# ADCAN__sch2.net
KiCad netlist of a schematic drawn in Altium Designer
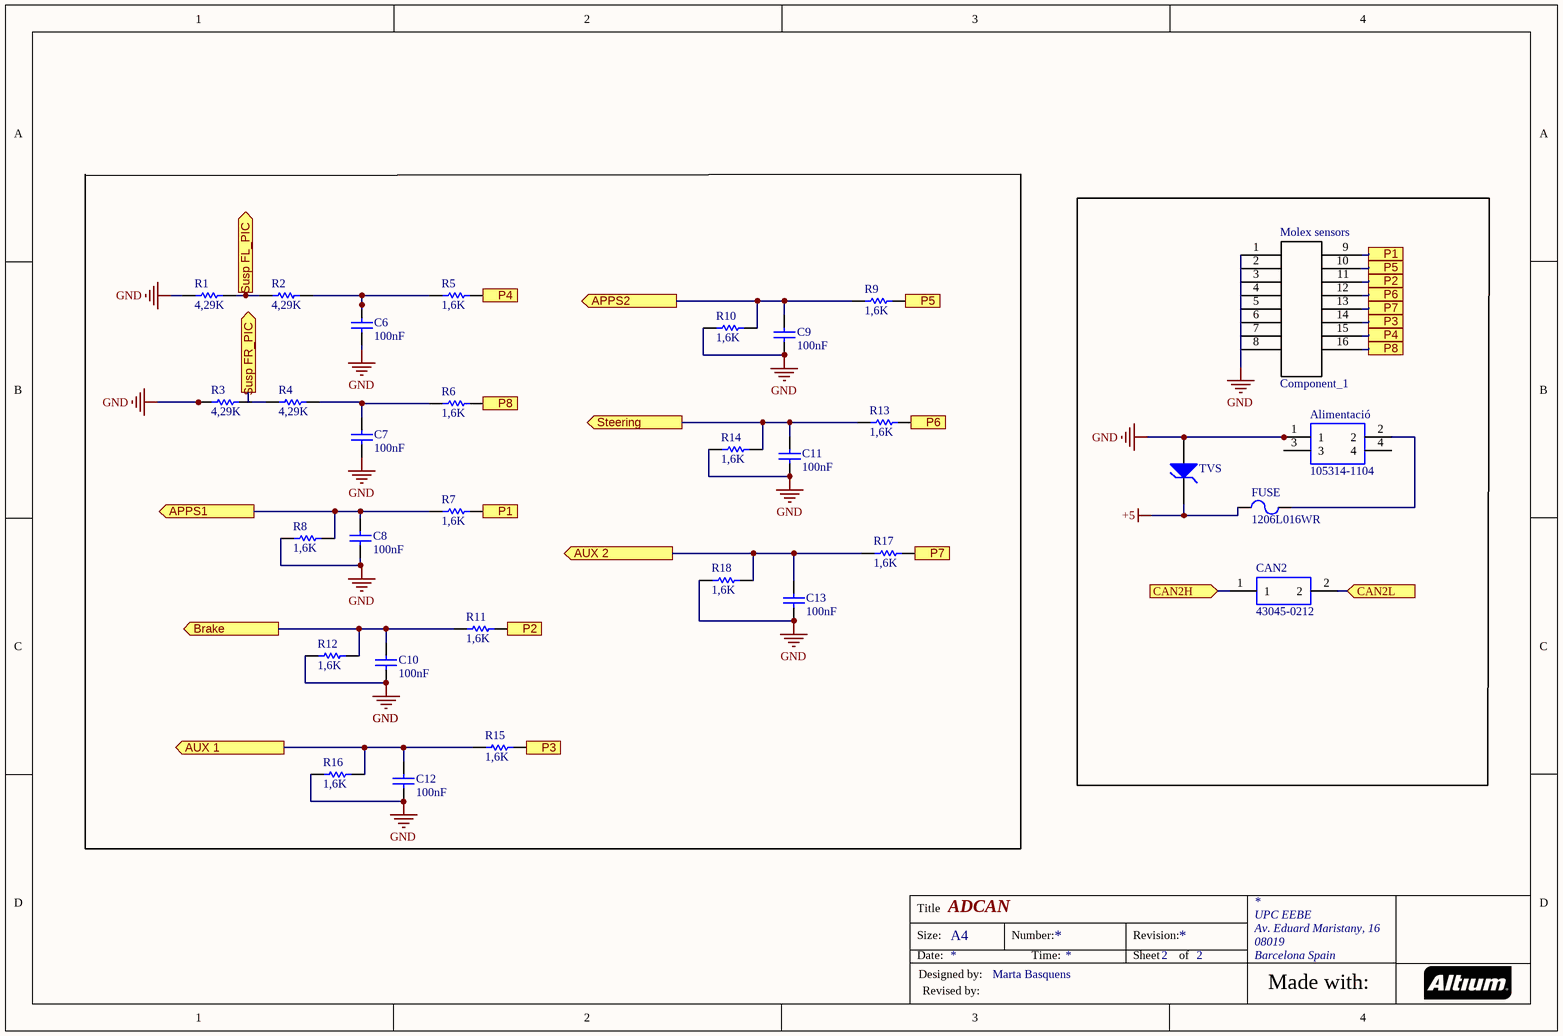
[diagram p0: ADCAN_[sch2].SchDoc]

(export (version "E")
  (design (tool "Eeschema 10.0.6"))
  (components
    (comp (ref "Alimentació")
      (value "105314-1104")
      (footprint "1053141304")
      (description "Molex Nano-Fit 105314, 2.5mm Pitch, 4 Way, 2 Row, Right Angle PCB Header, Through Hole")
      (fields (field (name "RS PART NUMBER") "1623690"))
      (libsource (lib "105314-1104") (part "105314-1104"))
    )
    (comp (ref "C6")
      (value "100nF")
      (footprint "CAPC3216X102X94LL20")
      (description "Chip Capacitor, 1.05 nF, +/- 12%, 14 V, -55 to 125 degC, 1206 (3216 Metric), RoHS, Tape and Reel")
      (fields (field (name "MANUFACTURER") "AVX"))
      (libsource (lib "Altium Content Vault") (part "CAP-NP-2"))
    )
    (comp (ref "C7")
      (value "100nF")
      (footprint "CAPC3216X102X94LL20")
      (description "Chip Capacitor, 1.05 nF, +/- 12%, 14 V, -55 to 125 degC, 1206 (3216 Metric), RoHS, Tape and Reel")
      (fields (field (name "MANUFACTURER") "AVX"))
      (libsource (lib "Altium Content Vault") (part "CAP-NP-2"))
    )
    (comp (ref "C8")
      (value "100nF")
      (footprint "CAPC3216X102X94LL20")
      (description "Chip Capacitor, 1.05 nF, +/- 12%, 14 V, -55 to 125 degC, 1206 (3216 Metric), RoHS, Tape and Reel")
      (fields (field (name "MANUFACTURER") "AVX"))
      (libsource (lib "Altium Content Vault") (part "CAP-NP-2"))
    )
    (comp (ref "C9")
      (value "100nF")
      (footprint "CAPC3216X102X94LL20")
      (description "Chip Capacitor, 1.05 nF, +/- 12%, 14 V, -55 to 125 degC, 1206 (3216 Metric), RoHS, Tape and Reel")
      (fields (field (name "MANUFACTURER") "AVX"))
      (libsource (lib "Altium Content Vault") (part "CAP-NP-2"))
    )
    (comp (ref "C10")
      (value "100nF")
      (footprint "CAPC3216X102X94LL20")
      (description "Chip Capacitor, 1.05 nF, +/- 12%, 14 V, -55 to 125 degC, 1206 (3216 Metric), RoHS, Tape and Reel")
      (fields (field (name "MANUFACTURER") "AVX"))
      (libsource (lib "Altium Content Vault") (part "CAP-NP-2"))
    )
    (comp (ref "C11")
      (value "100nF")
      (footprint "CAPC3216X102X94LL20")
      (description "Chip Capacitor, 1.05 nF, +/- 12%, 14 V, -55 to 125 degC, 1206 (3216 Metric), RoHS, Tape and Reel")
      (fields (field (name "MANUFACTURER") "AVX"))
      (libsource (lib "Altium Content Vault") (part "CAP-NP-2"))
    )
    (comp (ref "C12")
      (value "100nF")
      (footprint "CAPC3216X102X94LL20")
      (description "Chip Capacitor, 1.05 nF, +/- 12%, 14 V, -55 to 125 degC, 1206 (3216 Metric), RoHS, Tape and Reel")
      (fields (field (name "MANUFACTURER") "AVX"))
      (libsource (lib "Altium Content Vault") (part "CAP-NP-2"))
    )
    (comp (ref "C13")
      (value "100nF")
      (footprint "CAPC3216X102X94LL20")
      (description "Chip Capacitor, 1.05 nF, +/- 12%, 14 V, -55 to 125 degC, 1206 (3216 Metric), RoHS, Tape and Reel")
      (fields (field (name "MANUFACTURER") "AVX"))
      (libsource (lib "Altium Content Vault") (part "CAP-NP-2"))
    )
    (comp (ref "CAN2")
      (value "43045-0212")
      (footprint "0430450212")
      (fields (field (name "RS PART NUMBER") "2332860P"))
      (libsource (lib "43045-0212") (part "43045-0212"))
    )
    (comp (ref "FUSE")
      (value "1206L016WR")
      (footprint "LFUS-1206L016WR_V")
      (description "Resettable Fuse, 30 V, 100 A, 4.5 Ohm, -40 to 85 degC, 1206 (3216 Metric), RoHS, Tape and Reel")
      (fields (field (name "MANUFACTURER") "Littelfuse"))
      (libsource (lib "Altium Content Vault") (part "FUSE-2"))
    )
    (comp (ref "Molex sensors")
      (value "Component_1")
      (footprint "Molex8x2:PCBComponent_1")
      (libsource (lib "Molex8x2") (part "Component_1"))
    )
    (comp (ref "R1")
      (value "4,29K")
      (footprint "RESC1206(3216)_L")
      (description "22K 0.25W 1% 1206 (3216 Metric)  SMD")
      (fields (field (name "TOLERANCE") "1 %") (field (name "POWER") "0.25 W"))
      (libsource (lib "") (part "RES_1"))
    )
    (comp (ref "R2")
      (value "4,29K")
      (footprint "RESC1206(3216)_L")
      (description "22K 0.25W 1% 1206 (3216 Metric)  SMD")
      (fields (field (name "TOLERANCE") "1 %") (field (name "POWER") "0.25 W"))
      (libsource (lib "") (part "RES_1"))
    )
    (comp (ref "R3")
      (value "4,29K")
      (footprint "RESC1206(3216)_L")
      (description "22K 0.25W 1% 1206 (3216 Metric)  SMD")
      (fields (field (name "TOLERANCE") "1 %") (field (name "POWER") "0.25 W"))
      (libsource (lib "") (part "RES_2"))
    )
    (comp (ref "R4")
      (value "4,29K")
      (footprint "RESC1206(3216)_L")
      (description "22K 0.25W 1% 1206 (3216 Metric)  SMD")
      (fields (field (name "TOLERANCE") "1 %") (field (name "POWER") "0.25 W"))
      (libsource (lib "") (part "RES_3"))
    )
    (comp (ref "R5")
      (value "1,6K")
      (footprint "RESC1206(3216)_L")
      (description "22K 0.25W 1% 1206 (3216 Metric)  SMD")
      (fields (field (name "TOLERANCE") "1 %") (field (name "POWER") "0.25 W"))
      (libsource (lib "Altium Content Vault") (part "RES"))
    )
    (comp (ref "R6")
      (value "1,6K")
      (footprint "RESC1206(3216)_L")
      (description "22K 0.25W 1% 1206 (3216 Metric)  SMD")
      (fields (field (name "TOLERANCE") "1 %") (field (name "POWER") "0.25 W"))
      (libsource (lib "Altium Content Vault") (part "RES"))
    )
    (comp (ref "R7")
      (value "1,6K")
      (footprint "RESC1206(3216)_L")
      (description "22K 0.25W 1% 1206 (3216 Metric)  SMD")
      (fields (field (name "TOLERANCE") "1 %") (field (name "POWER") "0.25 W"))
      (libsource (lib "Altium Content Vault") (part "RES"))
    )
    (comp (ref "R8")
      (value "1,6K")
      (footprint "RESC1206(3216)_L")
      (description "22K 0.25W 1% 1206 (3216 Metric)  SMD")
      (fields (field (name "TOLERANCE") "1 %") (field (name "POWER") "0.25 W"))
      (libsource (lib "Altium Content Vault") (part "RES"))
    )
    (comp (ref "R9")
      (value "1,6K")
      (footprint "RESC1206(3216)_L")
      (description "22K 0.25W 1% 1206 (3216 Metric)  SMD")
      (fields (field (name "TOLERANCE") "1 %") (field (name "POWER") "0.25 W"))
      (libsource (lib "Altium Content Vault") (part "RES"))
    )
    (comp (ref "R10")
      (value "1,6K")
      (footprint "RESC1206(3216)_L")
      (description "22K 0.25W 1% 1206 (3216 Metric)  SMD")
      (fields (field (name "TOLERANCE") "1 %") (field (name "POWER") "0.25 W"))
      (libsource (lib "Altium Content Vault") (part "RES"))
    )
    (comp (ref "R11")
      (value "1,6K")
      (footprint "RESC1206(3216)_L")
      (description "22K 0.25W 1% 1206 (3216 Metric)  SMD")
      (fields (field (name "TOLERANCE") "1 %") (field (name "POWER") "0.25 W"))
      (libsource (lib "Altium Content Vault") (part "RES"))
    )
    (comp (ref "R12")
      (value "1,6K")
      (footprint "RESC1206(3216)_L")
      (description "22K 0.25W 1% 1206 (3216 Metric)  SMD")
      (fields (field (name "TOLERANCE") "1 %") (field (name "POWER") "0.25 W"))
      (libsource (lib "Altium Content Vault") (part "RES"))
    )
    (comp (ref "R13")
      (value "1,6K")
      (footprint "RESC1206(3216)_L")
      (description "22K 0.25W 1% 1206 (3216 Metric)  SMD")
      (fields (field (name "TOLERANCE") "1 %") (field (name "POWER") "0.25 W"))
      (libsource (lib "Altium Content Vault") (part "RES"))
    )
    (comp (ref "R14")
      (value "1,6K")
      (footprint "RESC1206(3216)_L")
      (description "22K 0.25W 1% 1206 (3216 Metric)  SMD")
      (fields (field (name "TOLERANCE") "1 %") (field (name "POWER") "0.25 W"))
      (libsource (lib "Altium Content Vault") (part "RES"))
    )
    (comp (ref "R15")
      (value "1,6K")
      (footprint "RESC1206(3216)_L")
      (description "22K 0.25W 1% 1206 (3216 Metric)  SMD")
      (fields (field (name "TOLERANCE") "1 %") (field (name "POWER") "0.25 W"))
      (libsource (lib "Altium Content Vault") (part "RES"))
    )
    (comp (ref "R16")
      (value "1,6K")
      (footprint "RESC1206(3216)_L")
      (description "22K 0.25W 1% 1206 (3216 Metric)  SMD")
      (fields (field (name "TOLERANCE") "1 %") (field (name "POWER") "0.25 W"))
      (libsource (lib "Altium Content Vault") (part "RES"))
    )
    (comp (ref "R17")
      (value "1,6K")
      (footprint "RESC1206(3216)_L")
      (description "22K 0.25W 1% 1206 (3216 Metric)  SMD")
      (fields (field (name "TOLERANCE") "1 %") (field (name "POWER") "0.25 W"))
      (libsource (lib "Altium Content Vault") (part "RES"))
    )
    (comp (ref "R18")
      (value "1,6K")
      (footprint "RESC1206(3216)_L")
      (description "22K 0.25W 1% 1206 (3216 Metric)  SMD")
      (fields (field (name "TOLERANCE") "1 %") (field (name "POWER") "0.25 W"))
      (libsource (lib "Altium Content Vault") (part "RES"))
    )
    (comp (ref "TVS")
      (value "~")
      (footprint "ONSC-SMB-2-403A-03_J_V")
      (description "TVS ZENER UNIDIR 600W 27V SMB")
      (fields (field (name "PARTNUMBER") "P6SMB27AT3G"))
      (libsource (lib "Altium Content Vault") (part "Zener-AC-2"))
    )
  )
  (nets
    (net (code "1") (name "+5") (class "Default")
      (node (ref "FUSE") (pin "1") (pinfunction "1_1") (pintype "passive"))
      (node (ref "TVS") (pin "C") (pinfunction "C_C") (pintype "passive"))
    )
    (net (code "2") (name "/APPS1") (class "Default")
      (node (ref "C8") (pin "2") (pinfunction "2_2") (pintype "passive"))
      (node (ref "R7") (pin "2") (pinfunction "2_2") (pintype "passive"))
      (node (ref "R8") (pin "1") (pinfunction "1_1") (pintype "passive"))
    )
    (net (code "3") (name "/APPS2") (class "Default")
      (node (ref "C9") (pin "2") (pinfunction "2_2") (pintype "passive"))
      (node (ref "R10") (pin "1") (pinfunction "1_1") (pintype "passive"))
      (node (ref "R9") (pin "2") (pinfunction "2_2") (pintype "passive"))
    )
    (net (code "4") (name "/AUX 1") (class "Default")
      (node (ref "C12") (pin "2") (pinfunction "2_2") (pintype "passive"))
      (node (ref "R15") (pin "2") (pinfunction "2_2") (pintype "passive"))
      (node (ref "R16") (pin "1") (pinfunction "1_1") (pintype "passive"))
    )
    (net (code "5") (name "/AUX 2") (class "Default")
      (node (ref "C13") (pin "2") (pinfunction "2_2") (pintype "passive"))
      (node (ref "R17") (pin "2") (pinfunction "2_2") (pintype "passive"))
      (node (ref "R18") (pin "1") (pinfunction "1_1") (pintype "passive"))
    )
    (net (code "6") (name "/Brake") (class "Default")
      (node (ref "C10") (pin "2") (pinfunction "2_2") (pintype "passive"))
      (node (ref "R11") (pin "2") (pinfunction "2_2") (pintype "passive"))
      (node (ref "R12") (pin "1") (pinfunction "1_1") (pintype "passive"))
    )
    (net (code "7") (name "/CAN2H") (class "Default")
      (node (ref "CAN2") (pin "1") (pinfunction "1_1") (pintype "passive"))
    )
    (net (code "8") (name "/CAN2L") (class "Default")
      (node (ref "CAN2") (pin "2") (pinfunction "2_2") (pintype "passive"))
    )
    (net (code "9") (name "/P1") (class "Default")
      (node (ref "R7") (pin "1") (pinfunction "1_1") (pintype "passive"))
    )
    (net (code "10") (name "/P2") (class "Default")
      (node (ref "R11") (pin "1") (pinfunction "1_1") (pintype "passive"))
    )
    (net (code "11") (name "/P3") (class "Default")
      (node (ref "R15") (pin "1") (pinfunction "1_1") (pintype "passive"))
    )
    (net (code "12") (name "/P4") (class "Default")
      (node (ref "R5") (pin "1") (pinfunction "1_1") (pintype "passive"))
    )
    (net (code "13") (name "/P5") (class "Default")
      (node (ref "R9") (pin "1") (pinfunction "1_1") (pintype "passive"))
    )
    (net (code "14") (name "/P6") (class "Default")
      (node (ref "R13") (pin "1") (pinfunction "1_1") (pintype "passive"))
    )
    (net (code "15") (name "/P7") (class "Default")
      (node (ref "R17") (pin "1") (pinfunction "1_1") (pintype "passive"))
    )
    (net (code "16") (name "/P8") (class "Default")
      (node (ref "R6") (pin "1") (pinfunction "1_1") (pintype "passive"))
    )
    (net (code "17") (name "/Steering") (class "Default")
      (node (ref "C11") (pin "2") (pinfunction "2_2") (pintype "passive"))
      (node (ref "R13") (pin "2") (pinfunction "2_2") (pintype "passive"))
      (node (ref "R14") (pin "1") (pinfunction "1_1") (pintype "passive"))
    )
    (net (code "18") (name "/Susp FL_PIC") (class "Default")
      (node (ref "R1") (pin "2") (pinfunction "2_2") (pintype "passive"))
      (node (ref "R2") (pin "1") (pinfunction "1_1") (pintype "passive"))
    )
    (net (code "20") (name "GND") (class "Default")
      (node (ref "Alimentació") (pin "1") (pinfunction "1_1") (pintype "passive"))
      (node (ref "C10") (pin "1") (pinfunction "1_1") (pintype "passive"))
      (node (ref "C11") (pin "1") (pinfunction "1_1") (pintype "passive"))
      (node (ref "C12") (pin "1") (pinfunction "1_1") (pintype "passive"))
      (node (ref "C13") (pin "1") (pinfunction "1_1") (pintype "passive"))
      (node (ref "C6") (pin "1") (pinfunction "1_1") (pintype "passive"))
      (node (ref "C7") (pin "1") (pinfunction "1_1") (pintype "passive"))
      (node (ref "C8") (pin "1") (pinfunction "1_1") (pintype "passive"))
      (node (ref "C9") (pin "1") (pinfunction "1_1") (pintype "passive"))
      (node (ref "R1") (pin "1") (pinfunction "1_1") (pintype "passive"))
      (node (ref "R10") (pin "2") (pinfunction "2_2") (pintype "passive"))
      (node (ref "R12") (pin "2") (pinfunction "2_2") (pintype "passive"))
      (node (ref "R14") (pin "2") (pinfunction "2_2") (pintype "passive"))
      (node (ref "R16") (pin "2") (pinfunction "2_2") (pintype "passive"))
      (node (ref "R18") (pin "2") (pinfunction "2_2") (pintype "passive"))
      (node (ref "R3") (pin "1") (pinfunction "1_1") (pintype "passive"))
      (node (ref "R8") (pin "2") (pinfunction "2_2") (pintype "passive"))
      (node (ref "TVS") (pin "A") (pinfunction "A_A") (pintype "passive"))
    )
    (net (code "21") (name "Net-(Alimentació-Pad2)") (class "Default")
      (node (ref "Alimentació") (pin "2") (pinfunction "2_2") (pintype "passive"))
      (node (ref "FUSE") (pin "2") (pinfunction "2_2") (pintype "passive"))
    )
    (net (code "22") (name "Net-(C6-Pad2)") (class "Default")
      (node (ref "C6") (pin "2") (pinfunction "2_2") (pintype "passive"))
      (node (ref "R2") (pin "2") (pinfunction "2_2") (pintype "passive"))
      (node (ref "R5") (pin "2") (pinfunction "2_2") (pintype "passive"))
    )
    (net (code "23") (name "Net-(C7-Pad2)") (class "Default")
      (node (ref "C7") (pin "2") (pinfunction "2_2") (pintype "passive"))
      (node (ref "R4") (pin "2") (pinfunction "2_2") (pintype "passive"))
      (node (ref "R6") (pin "2") (pinfunction "2_2") (pintype "passive"))
    )
    (net (code "24") (name "Net-(R3-Pad1)") (class "Default")
      (node (ref "R3") (pin "1") (pinfunction "1_1") (pintype "passive"))
      (node (ref "R4") (pin "2") (pinfunction "2_2") (pintype "passive"))
    )
    (net (code "25") (name "unconnected-(Alimentació-Pad3)") (class "Default")
      (node (ref "Alimentació") (pin "3") (pinfunction "3_3") (pintype "passive"))
    )
    (net (code "26") (name "unconnected-(Alimentació-Pad4)") (class "Default")
      (node (ref "Alimentació") (pin "4") (pinfunction "4_4") (pintype "passive"))
    )
    (net (code "27") (name "unconnected-(Molex sensors-Pad1)") (class "Default")
      (node (ref "Molex sensors") (pin "1") (pintype "passive"))
    )
    (net (code "28") (name "unconnected-(Molex sensors-Pad2)") (class "Default")
      (node (ref "Molex sensors") (pin "2") (pintype "passive"))
    )
    (net (code "29") (name "unconnected-(Molex sensors-Pad3)") (class "Default")
      (node (ref "Molex sensors") (pin "3") (pintype "passive"))
    )
    (net (code "30") (name "unconnected-(Molex sensors-Pad4)") (class "Default")
      (node (ref "Molex sensors") (pin "4") (pintype "passive"))
    )
    (net (code "31") (name "unconnected-(Molex sensors-Pad5)") (class "Default")
      (node (ref "Molex sensors") (pin "5") (pintype "passive"))
    )
    (net (code "32") (name "unconnected-(Molex sensors-Pad6)") (class "Default")
      (node (ref "Molex sensors") (pin "6") (pintype "passive"))
    )
    (net (code "33") (name "unconnected-(Molex sensors-Pad7)") (class "Default")
      (node (ref "Molex sensors") (pin "7") (pintype "passive"))
    )
    (net (code "34") (name "unconnected-(Molex sensors-Pad8)") (class "Default")
      (node (ref "Molex sensors") (pin "8") (pintype "passive"))
    )
    (net (code "35") (name "unconnected-(Molex sensors-Pad9)") (class "Default")
      (node (ref "Molex sensors") (pin "9") (pintype "passive"))
    )
    (net (code "36") (name "unconnected-(Molex sensors-Pad10)") (class "Default")
      (node (ref "Molex sensors") (pin "10") (pintype "passive"))
    )
    (net (code "37") (name "unconnected-(Molex sensors-Pad11)") (class "Default")
      (node (ref "Molex sensors") (pin "11") (pintype "passive"))
    )
    (net (code "38") (name "unconnected-(Molex sensors-Pad12)") (class "Default")
      (node (ref "Molex sensors") (pin "12") (pintype "passive"))
    )
    (net (code "39") (name "unconnected-(Molex sensors-Pad13)") (class "Default")
      (node (ref "Molex sensors") (pin "13") (pintype "passive"))
    )
    (net (code "40") (name "unconnected-(Molex sensors-Pad14)") (class "Default")
      (node (ref "Molex sensors") (pin "14") (pintype "passive"))
    )
    (net (code "41") (name "unconnected-(Molex sensors-Pad15)") (class "Default")
      (node (ref "Molex sensors") (pin "15") (pintype "passive"))
    )
    (net (code "42") (name "unconnected-(Molex sensors-Pad16)") (class "Default")
      (node (ref "Molex sensors") (pin "16") (pintype "passive"))
    )
  )
)
